# Generic_Module.net
KiCad netlist of a schematic drawn in Altium Designer
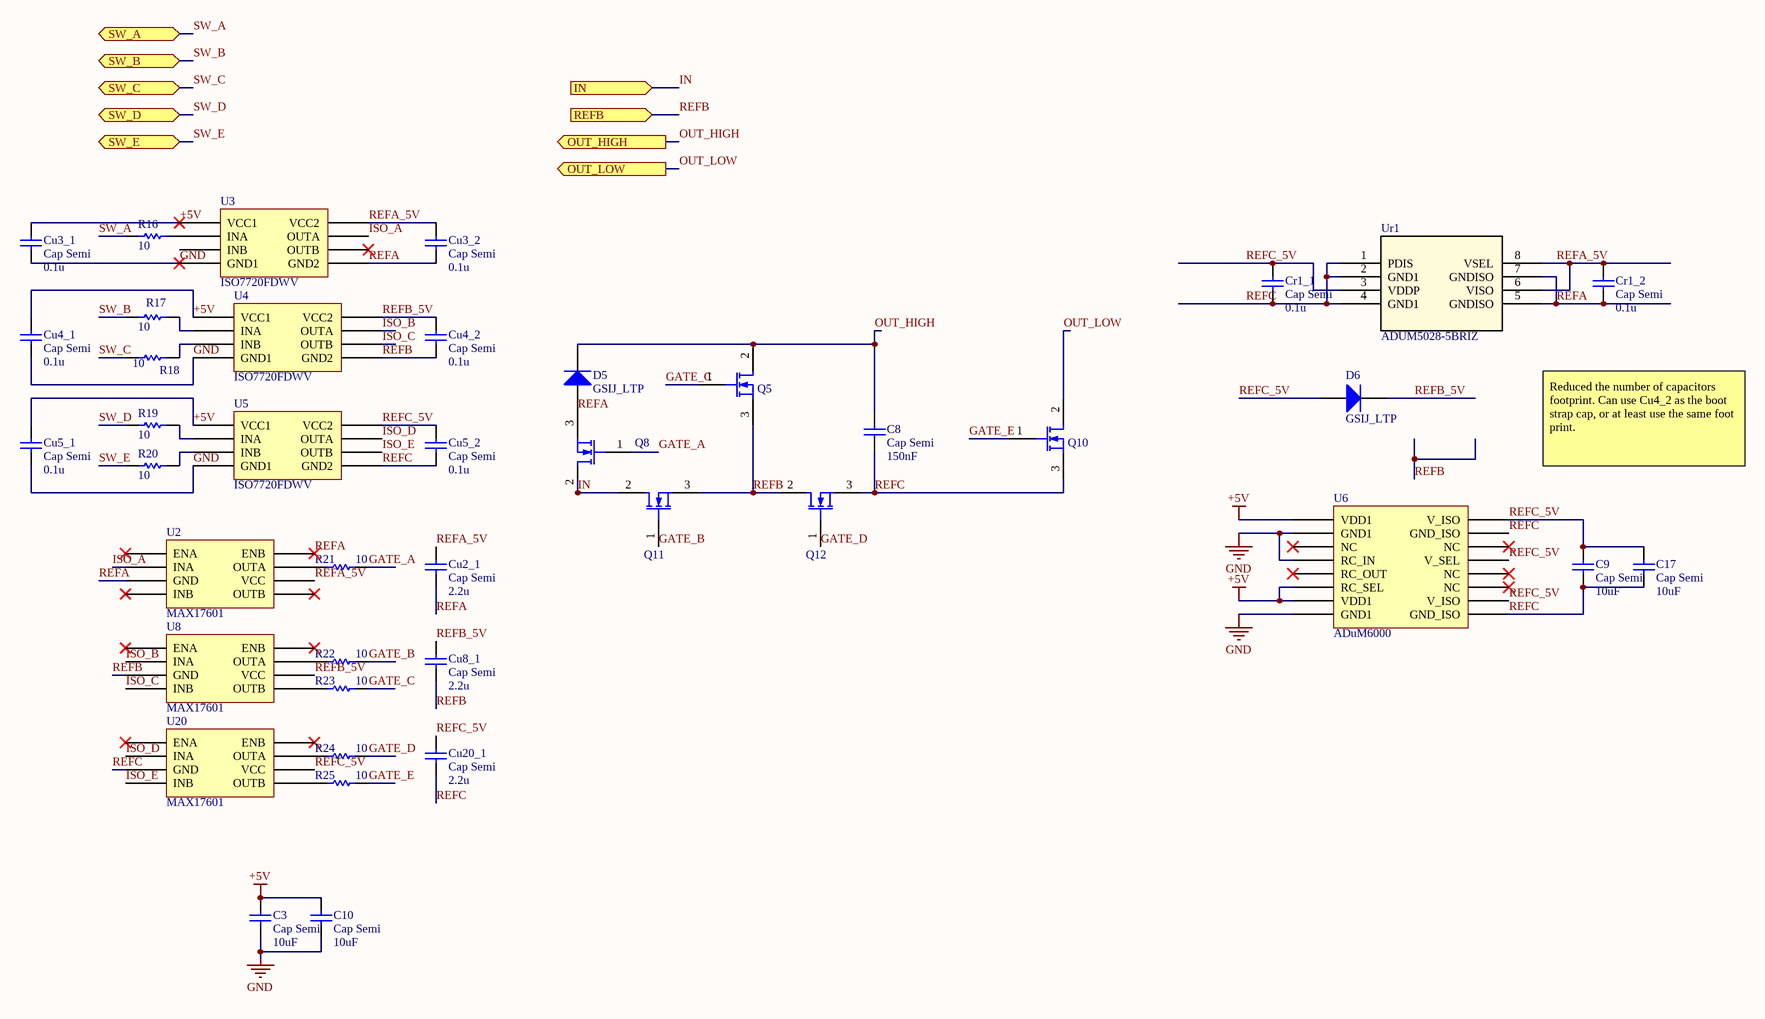
[diagram p0: Generic_Module.SchDoc]

(export (version "E")
  (design (tool "Eeschema 10.0.6"))
  (components
    (comp (ref "C3")
      (value "Cap Semi")
      (footprint "1608[0603]")
      (description "Capacitor (Semiconductor SIM Model)")
      (fields (field (name "ALTIUM_VALUE") "10uF") (field (name "PUBLISHER") "Altium Limited"))
      (libsource (lib "Miscellaneous Devices") (part "Cap Semi"))
    )
    (comp (ref "C8")
      (value "Cap Semi")
      (footprint "1812")
      (description "Capacitor (Semiconductor SIM Model)")
      (fields (field (name "ALTIUM_VALUE") "150nF") (field (name "PUBLISHER") "Altium Limited"))
      (libsource (lib "Miscellaneous Devices") (part "Cap Semi"))
    )
    (comp (ref "C9")
      (value "Cap Semi")
      (footprint "J1-0603")
      (description "Capacitor (Semiconductor SIM Model)")
      (fields (field (name "ALTIUM_VALUE") "10uF") (field (name "PUBLISHER") "Altium Limited"))
      (libsource (lib "Miscellaneous Devices") (part "Cap Semi"))
    )
    (comp (ref "C10")
      (value "Cap Semi")
      (footprint "1608[0603]")
      (description "Capacitor (Semiconductor SIM Model)")
      (fields (field (name "ALTIUM_VALUE") "10uF") (field (name "PUBLISHER") "Altium Limited"))
      (libsource (lib "Miscellaneous Devices") (part "Cap Semi"))
    )
    (comp (ref "C17")
      (value "Cap Semi")
      (footprint "J1-0603")
      (description "Capacitor (Semiconductor SIM Model)")
      (fields (field (name "ALTIUM_VALUE") "10uF") (field (name "PUBLISHER") "Altium Limited"))
      (libsource (lib "Miscellaneous Devices") (part "Cap Semi"))
    )
    (comp (ref "Cr1_1")
      (value "Cap Semi")
      (footprint "J1-0603")
      (description "Capacitor (Semiconductor SIM Model)")
      (fields (field (name "ALTIUM_VALUE") "0.1u") (field (name "PUBLISHER") "Altium Limited"))
      (libsource (lib "Miscellaneous Devices") (part "Cap Semi"))
    )
    (comp (ref "Cr1_2")
      (value "Cap Semi")
      (footprint "J1-0603")
      (description "Capacitor (Semiconductor SIM Model)")
      (fields (field (name "ALTIUM_VALUE") "0.1u") (field (name "PUBLISHER") "Altium Limited"))
      (libsource (lib "Miscellaneous Devices") (part "Cap Semi"))
    )
    (comp (ref "Cu2_1")
      (value "Cap Semi")
      (footprint "1608[0603]")
      (description "Capacitor (Semiconductor SIM Model)")
      (fields (field (name "ALTIUM_VALUE") "2.2u") (field (name "PUBLISHER") "Altium Limited"))
      (libsource (lib "SCMLI_V3_1") (part "Cap Semi"))
    )
    (comp (ref "Cu3_1")
      (value "Cap Semi")
      (footprint "C1206")
      (description "Capacitor (Semiconductor SIM Model)")
      (fields (field (name "ALTIUM_VALUE") "0.1u") (field (name "PUBLISHER") "Altium Limited"))
      (libsource (lib "SCMLI_V3_1") (part "Cap Semi"))
    )
    (comp (ref "Cu3_2")
      (value "Cap Semi")
      (footprint "C1206")
      (description "Capacitor (Semiconductor SIM Model)")
      (fields (field (name "ALTIUM_VALUE") "0.1u") (field (name "PUBLISHER") "Altium Limited"))
      (libsource (lib "SCMLI_V3_1") (part "Cap Semi"))
    )
    (comp (ref "Cu4_1")
      (value "Cap Semi")
      (footprint "C1206")
      (description "Capacitor (Semiconductor SIM Model)")
      (fields (field (name "ALTIUM_VALUE") "0.1u") (field (name "PUBLISHER") "Altium Limited"))
      (libsource (lib "SCMLI_V3_1") (part "Cap Semi"))
    )
    (comp (ref "Cu4_2")
      (value "Cap Semi")
      (footprint "C1206")
      (description "Capacitor (Semiconductor SIM Model)")
      (fields (field (name "ALTIUM_VALUE") "0.1u") (field (name "PUBLISHER") "Altium Limited"))
      (libsource (lib "SCMLI_V3_1") (part "Cap Semi"))
    )
    (comp (ref "Cu5_1")
      (value "Cap Semi")
      (footprint "C1206")
      (description "Capacitor (Semiconductor SIM Model)")
      (fields (field (name "ALTIUM_VALUE") "0.1u") (field (name "PUBLISHER") "Altium Limited"))
      (libsource (lib "SCMLI_V3_1") (part "Cap Semi"))
    )
    (comp (ref "Cu5_2")
      (value "Cap Semi")
      (footprint "C1206")
      (description "Capacitor (Semiconductor SIM Model)")
      (fields (field (name "ALTIUM_VALUE") "0.1u") (field (name "PUBLISHER") "Altium Limited"))
      (libsource (lib "SCMLI_V3_1") (part "Cap Semi"))
    )
    (comp (ref "Cu8_1")
      (value "Cap Semi")
      (footprint "1608[0603]")
      (description "Capacitor (Semiconductor SIM Model)")
      (fields (field (name "ALTIUM_VALUE") "2.2u") (field (name "PUBLISHER") "Altium Limited"))
      (libsource (lib "SCMLI_V3_1") (part "Cap Semi"))
    )
    (comp (ref "Cu20_1")
      (value "Cap Semi")
      (footprint "1608[0603]")
      (description "Capacitor (Semiconductor SIM Model)")
      (fields (field (name "ALTIUM_VALUE") "2.2u") (field (name "PUBLISHER") "Altium Limited"))
      (libsource (lib "SCMLI_V3_1") (part "Cap Semi"))
    )
    (comp (ref "D5")
      (value "GSIJ_LTP")
      (footprint "SE30PAJ-M3")
      (libsource (lib "SCMLI_V3") (part "SE30PAJ-M3"))
    )
    (comp (ref "D6")
      (value "GSIJ_LTP")
      (footprint "SE30PAJ-M3")
      (libsource (lib "SCMLI_V3") (part "SE30PAJ-M3"))
    )
    (comp (ref "Q5")
      (value "IPN80R1K2P7")
      (footprint "SOT233-3")
      (libsource (lib "SCMLI_V3") (part "IPN80R1K2P7"))
    )
    (comp (ref "Q8")
      (value "IPN80R1K2P7")
      (footprint "SOT233-3")
      (libsource (lib "SCMLI_V3") (part "IPN80R1K2P7"))
    )
    (comp (ref "Q10")
      (value "IPN80R1K2P7")
      (footprint "SOT233-3")
      (libsource (lib "SCMLI_V3") (part "IPN80R1K2P7"))
    )
    (comp (ref "Q11")
      (value "IPN80R1K2P7")
      (footprint "SOT233-3")
      (libsource (lib "SCMLI_V3") (part "IPN80R1K2P7"))
    )
    (comp (ref "Q12")
      (value "IPN80R1K2P7")
      (footprint "SOT233-3")
      (libsource (lib "SCMLI_V3") (part "IPN80R1K2P7"))
    )
    (comp (ref "R16")
      (value "10")
      (footprint "1608[0603]")
      (description "Resistor 0402 / 0603 / 0805")
      (libsource (lib "Miscellaneous Devices") (part "Res1"))
    )
    (comp (ref "R17")
      (value "10")
      (footprint "1608[0603]")
      (description "Resistor 0402 / 0603 / 0805")
      (libsource (lib "Miscellaneous Devices") (part "Res1"))
    )
    (comp (ref "R18")
      (value "10")
      (footprint "1608[0603]")
      (description "Resistor 0402 / 0603 / 0805")
      (libsource (lib "Miscellaneous Devices") (part "Res1"))
    )
    (comp (ref "R19")
      (value "10")
      (footprint "1608[0603]")
      (description "Resistor 0402 / 0603 / 0805")
      (libsource (lib "Miscellaneous Devices") (part "Res1"))
    )
    (comp (ref "R20")
      (value "10")
      (footprint "1608[0603]")
      (description "Resistor 0402 / 0603 / 0805")
      (libsource (lib "Miscellaneous Devices") (part "Res1"))
    )
    (comp (ref "R21")
      (value "10")
      (footprint "1608[0603]")
      (description "Resistor 0402 / 0603 / 0805")
      (libsource (lib "Miscellaneous Devices") (part "Res1"))
    )
    (comp (ref "R22")
      (value "10")
      (footprint "1608[0603]")
      (description "Resistor 0402 / 0603 / 0805")
      (libsource (lib "Miscellaneous Devices") (part "Res1"))
    )
    (comp (ref "R23")
      (value "10")
      (footprint "1608[0603]")
      (description "Resistor 0402 / 0603 / 0805")
      (libsource (lib "Miscellaneous Devices") (part "Res1"))
    )
    (comp (ref "R24")
      (value "10")
      (footprint "1608[0603]")
      (description "Resistor 0402 / 0603 / 0805")
      (libsource (lib "Miscellaneous Devices") (part "Res1"))
    )
    (comp (ref "R25")
      (value "10")
      (footprint "1608[0603]")
      (description "Resistor 0402 / 0603 / 0805")
      (libsource (lib "Miscellaneous Devices") (part "Res1"))
    )
    (comp (ref "U2")
      (value "MAX17601")
      (footprint "DFN-8_DD")
      (libsource (lib "SCMLI_V3_1") (part "MAX17601"))
    )
    (comp (ref "U3")
      (value "ISO7720FDWV")
      (footprint "TI_DWV")
      (libsource (lib "SCMLI_V3_1") (part "ISO7720FDWV"))
    )
    (comp (ref "U4")
      (value "ISO7720FDWV")
      (footprint "TI_DWV")
      (libsource (lib "SCMLI_V3_1") (part "ISO7720FDWV"))
    )
    (comp (ref "U5")
      (value "ISO7720FDWV")
      (footprint "TI_DWV")
      (libsource (lib "SCMLI_V3_1") (part "ISO7720FDWV"))
    )
    (comp (ref "U6")
      (value "ADuM6000")
      (footprint "SOIC127P1030X265-16N")
      (description "Isolatd 5V-5V DCDC power supply")
      (libsource (lib "SCMLI_V3") (part "ADuM6000"))
    )
    (comp (ref "U8")
      (value "MAX17601")
      (footprint "DFN-8_DD")
      (libsource (lib "SCMLI_V3_1") (part "MAX17601"))
    )
    (comp (ref "U20")
      (value "MAX17601")
      (footprint "DFN-8_DD")
      (libsource (lib "SCMLI_V3_1") (part "MAX17601"))
    )
    (comp (ref "Ur1")
      (value "ADUM5028-5BRIZ")
      (footprint "RI_8_1")
      (description "No Description Available")
      (fields (field (name "COPYRIGHT") "Copyright (C) 2018 Accelerated Designs. All rights reserved"))
      (libsource (lib "SCMLI_V3_1") (part "ADUM5028-5BRIZ"))
    )
  )
  (nets
    (net (code "1") (name "+5V") (class "Default")
      (node (ref "C10") (pin "2") (pinfunction "2_2") (pintype "passive"))
      (node (ref "C3") (pin "2") (pinfunction "2_2") (pintype "passive"))
      (node (ref "Cu3_1") (pin "2") (pinfunction "2_2") (pintype "passive"))
      (node (ref "Cu4_1") (pin "2") (pinfunction "2_2") (pintype "passive"))
      (node (ref "Cu5_1") (pin "2") (pinfunction "2_2") (pintype "passive"))
      (node (ref "U3") (pin "1") (pinfunction "VCC1_1") (pintype "passive"))
      (node (ref "U4") (pin "1") (pinfunction "VCC1_1") (pintype "passive"))
      (node (ref "U5") (pin "1") (pinfunction "VCC1_1") (pintype "passive"))
      (node (ref "U6") (pin "1") (pinfunction "VDD1_1") (pintype "passive"))
      (node (ref "U6") (pin "6") (pinfunction "RC_SEL_6") (pintype "passive"))
      (node (ref "U6") (pin "7") (pinfunction "VDD1_7") (pintype "passive"))
    )
    (net (code "2") (name "/GATE_A") (class "Default")
      (node (ref "Q8") (pin "1") (pinfunction "1_1") (pintype "passive"))
      (node (ref "R21") (pin "2") (pinfunction "2_2") (pintype "passive"))
    )
    (net (code "3") (name "/GATE_B") (class "Default")
      (node (ref "Q11") (pin "1") (pinfunction "1_1") (pintype "passive"))
      (node (ref "R22") (pin "2") (pinfunction "2_2") (pintype "passive"))
    )
    (net (code "4") (name "/GATE_C") (class "Default")
      (node (ref "Q5") (pin "1") (pinfunction "1_1") (pintype "passive"))
      (node (ref "R23") (pin "2") (pinfunction "2_2") (pintype "passive"))
    )
    (net (code "5") (name "/GATE_D") (class "Default")
      (node (ref "Q12") (pin "1") (pinfunction "1_1") (pintype "passive"))
      (node (ref "R24") (pin "2") (pinfunction "2_2") (pintype "passive"))
    )
    (net (code "6") (name "/GATE_E") (class "Default")
      (node (ref "Q10") (pin "1") (pinfunction "1_1") (pintype "passive"))
      (node (ref "R25") (pin "2") (pinfunction "2_2") (pintype "passive"))
    )
    (net (code "7") (name "/IN") (class "Default")
      (node (ref "Q11") (pin "2") (pinfunction "2_2") (pintype "passive"))
      (node (ref "Q8") (pin "2") (pinfunction "2_2") (pintype "passive"))
    )
    (net (code "8") (name "/ISO_A") (class "Default")
      (node (ref "U2") (pin "2") (pinfunction "INA_2") (pintype "passive"))
      (node (ref "U3") (pin "7") (pinfunction "OUTA_7") (pintype "passive"))
    )
    (net (code "9") (name "/ISO_B") (class "Default")
      (node (ref "U4") (pin "7") (pinfunction "OUTA_7") (pintype "passive"))
      (node (ref "U8") (pin "2") (pinfunction "INA_2") (pintype "passive"))
    )
    (net (code "10") (name "/ISO_C") (class "Default")
      (node (ref "U4") (pin "6") (pinfunction "OUTB_6") (pintype "passive"))
      (node (ref "U8") (pin "4") (pinfunction "INB_4") (pintype "passive"))
    )
    (net (code "11") (name "/ISO_D") (class "Default")
      (node (ref "U20") (pin "2") (pinfunction "INA_2") (pintype "passive"))
      (node (ref "U5") (pin "7") (pinfunction "OUTA_7") (pintype "passive"))
    )
    (net (code "12") (name "/ISO_E") (class "Default")
      (node (ref "U20") (pin "4") (pinfunction "INB_4") (pintype "passive"))
      (node (ref "U5") (pin "6") (pinfunction "OUTB_6") (pintype "passive"))
    )
    (net (code "13") (name "/OUT_HIGH") (class "Default")
      (node (ref "C8") (pin "2") (pinfunction "2_2") (pintype "passive"))
      (node (ref "D5") (pin "2") (pinfunction "K_2") (pintype "passive"))
      (node (ref "Q5") (pin "2") (pinfunction "2_2") (pintype "passive"))
    )
    (net (code "14") (name "/OUT_LOW") (class "Default")
      (node (ref "Q10") (pin "2") (pinfunction "2_2") (pintype "passive"))
    )
    (net (code "15") (name "/REFA") (class "Default")
      (node (ref "Cr1_2") (pin "1") (pinfunction "1_1") (pintype "passive"))
      (node (ref "Cu2_1") (pin "1") (pinfunction "1_1") (pintype "passive"))
      (node (ref "Cu3_2") (pin "1") (pinfunction "1_1") (pintype "passive"))
      (node (ref "D5") (pin "1") (pinfunction "A_1") (pintype "passive"))
      (node (ref "Q8") (pin "3") (pinfunction "3_3") (pintype "passive"))
      (node (ref "U2") (pin "3") (pinfunction "GND_3") (pintype "passive"))
      (node (ref "U2") (pin "8") (pinfunction "ENB_8") (pintype "passive"))
      (node (ref "U3") (pin "5") (pinfunction "GND2_5") (pintype "passive"))
      (node (ref "Ur1") (pin "5") (pinfunction "GNDISO_5") (pintype "passive"))
      (node (ref "Ur1") (pin "7") (pinfunction "GNDISO_7") (pintype "passive"))
    )
    (net (code "16") (name "/REFA_5V") (class "Default")
      (node (ref "Cr1_2") (pin "2") (pinfunction "2_2") (pintype "passive"))
      (node (ref "Cu2_1") (pin "2") (pinfunction "2_2") (pintype "passive"))
      (node (ref "Cu3_2") (pin "2") (pinfunction "2_2") (pintype "passive"))
      (node (ref "U2") (pin "6") (pinfunction "VCC_6") (pintype "passive"))
      (node (ref "U3") (pin "8") (pinfunction "VCC2_8") (pintype "passive"))
      (node (ref "Ur1") (pin "6") (pinfunction "VISO_6") (pintype "passive"))
      (node (ref "Ur1") (pin "8") (pinfunction "VSEL_8") (pintype "passive"))
    )
    (net (code "17") (name "/REFB") (class "Default")
      (node (ref "Cu4_2") (pin "1") (pinfunction "1_1") (pintype "passive"))
      (node (ref "Cu8_1") (pin "1") (pinfunction "1_1") (pintype "passive"))
      (node (ref "Q11") (pin "3") (pinfunction "3_3") (pintype "passive"))
      (node (ref "Q12") (pin "2") (pinfunction "2_2") (pintype "passive"))
      (node (ref "Q5") (pin "3") (pinfunction "3_3") (pintype "passive"))
      (node (ref "U4") (pin "5") (pinfunction "GND2_5") (pintype "passive"))
      (node (ref "U8") (pin "3") (pinfunction "GND_3") (pintype "passive"))
    )
    (net (code "18") (name "/REFB_5V") (class "Default")
      (node (ref "Cu4_2") (pin "2") (pinfunction "2_2") (pintype "passive"))
      (node (ref "Cu8_1") (pin "2") (pinfunction "2_2") (pintype "passive"))
      (node (ref "D6") (pin "2") (pinfunction "K_2") (pintype "passive"))
      (node (ref "U4") (pin "8") (pinfunction "VCC2_8") (pintype "passive"))
      (node (ref "U8") (pin "6") (pinfunction "VCC_6") (pintype "passive"))
    )
    (net (code "19") (name "/REFC") (class "Default")
      (node (ref "C17") (pin "1") (pinfunction "1_1") (pintype "passive"))
      (node (ref "C8") (pin "1") (pinfunction "1_1") (pintype "passive"))
      (node (ref "C9") (pin "1") (pinfunction "1_1") (pintype "passive"))
      (node (ref "Cr1_1") (pin "1") (pinfunction "1_1") (pintype "passive"))
      (node (ref "Cu20_1") (pin "1") (pinfunction "1_1") (pintype "passive"))
      (node (ref "Cu5_2") (pin "1") (pinfunction "1_1") (pintype "passive"))
      (node (ref "Q10") (pin "3") (pinfunction "3_3") (pintype "passive"))
      (node (ref "Q12") (pin "3") (pinfunction "3_3") (pintype "passive"))
      (node (ref "U20") (pin "3") (pinfunction "GND_3") (pintype "passive"))
      (node (ref "U5") (pin "5") (pinfunction "GND2_5") (pintype "passive"))
      (node (ref "U6") (pin "15") (pinfunction "GND_ISO_15") (pintype "passive"))
      (node (ref "U6") (pin "9") (pinfunction "GND_ISO_9") (pintype "passive"))
      (node (ref "Ur1") (pin "1") (pinfunction "PDIS_1") (pintype "passive"))
      (node (ref "Ur1") (pin "2") (pinfunction "GND1_2") (pintype "passive"))
      (node (ref "Ur1") (pin "4") (pinfunction "GND1_4") (pintype "passive"))
    )
    (net (code "20") (name "/REFC_5V") (class "Default")
      (node (ref "C17") (pin "2") (pinfunction "2_2") (pintype "passive"))
      (node (ref "C9") (pin "2") (pinfunction "2_2") (pintype "passive"))
      (node (ref "Cr1_1") (pin "2") (pinfunction "2_2") (pintype "passive"))
      (node (ref "Cu20_1") (pin "2") (pinfunction "2_2") (pintype "passive"))
      (node (ref "Cu5_2") (pin "2") (pinfunction "2_2") (pintype "passive"))
      (node (ref "D6") (pin "1") (pinfunction "A_1") (pintype "passive"))
      (node (ref "U20") (pin "6") (pinfunction "VCC_6") (pintype "passive"))
      (node (ref "U5") (pin "8") (pinfunction "VCC2_8") (pintype "passive"))
      (node (ref "U6") (pin "10") (pinfunction "V_ISO_10") (pintype "passive"))
      (node (ref "U6") (pin "13") (pinfunction "V_SEL_13") (pintype "passive"))
      (node (ref "U6") (pin "16") (pinfunction "V_ISO_16") (pintype "passive"))
      (node (ref "Ur1") (pin "3") (pinfunction "VDDP_3") (pintype "passive"))
    )
    (net (code "21") (name "/SW_A") (class "Default")
      (node (ref "R16") (pin "2") (pinfunction "2_2") (pintype "passive"))
    )
    (net (code "22") (name "/SW_B") (class "Default")
      (node (ref "R17") (pin "2") (pinfunction "2_2") (pintype "passive"))
    )
    (net (code "23") (name "/SW_C") (class "Default")
      (node (ref "R18") (pin "1") (pinfunction "1_1") (pintype "passive"))
    )
    (net (code "24") (name "/SW_D") (class "Default")
      (node (ref "R19") (pin "2") (pinfunction "2_2") (pintype "passive"))
    )
    (net (code "25") (name "/SW_E") (class "Default")
      (node (ref "R20") (pin "2") (pinfunction "2_2") (pintype "passive"))
    )
    (net (code "26") (name "GND") (class "Default")
      (node (ref "C10") (pin "1") (pinfunction "1_1") (pintype "passive"))
      (node (ref "C3") (pin "1") (pinfunction "1_1") (pintype "passive"))
      (node (ref "Cu3_1") (pin "1") (pinfunction "1_1") (pintype "passive"))
      (node (ref "Cu4_1") (pin "1") (pinfunction "1_1") (pintype "passive"))
      (node (ref "Cu5_1") (pin "1") (pinfunction "1_1") (pintype "passive"))
      (node (ref "U3") (pin "4") (pinfunction "GND1_4") (pintype "passive"))
      (node (ref "U4") (pin "4") (pinfunction "GND1_4") (pintype "passive"))
      (node (ref "U5") (pin "4") (pinfunction "GND1_4") (pintype "passive"))
      (node (ref "U6") (pin "2") (pinfunction "GND1_2") (pintype "passive"))
      (node (ref "U6") (pin "4") (pinfunction "RC_IN_4") (pintype "passive"))
      (node (ref "U6") (pin "8") (pinfunction "GND1_8") (pintype "passive"))
    )
    (net (code "27") (name "Net-(U2-OUTA)") (class "Default")
      (node (ref "R21") (pin "1") (pinfunction "1_1") (pintype "passive"))
      (node (ref "U2") (pin "7") (pinfunction "OUTA_7") (pintype "passive"))
    )
    (net (code "28") (name "Net-(U3-INA)") (class "Default")
      (node (ref "R16") (pin "1") (pinfunction "1_1") (pintype "passive"))
      (node (ref "U3") (pin "2") (pinfunction "INA_2") (pintype "passive"))
    )
    (net (code "29") (name "Net-(U4-INA)") (class "Default")
      (node (ref "R17") (pin "1") (pinfunction "1_1") (pintype "passive"))
      (node (ref "U4") (pin "2") (pinfunction "INA_2") (pintype "passive"))
    )
    (net (code "30") (name "Net-(U4-INB)") (class "Default")
      (node (ref "R18") (pin "2") (pinfunction "2_2") (pintype "passive"))
      (node (ref "U4") (pin "3") (pinfunction "INB_3") (pintype "passive"))
    )
    (net (code "31") (name "Net-(U5-INA)") (class "Default")
      (node (ref "R19") (pin "1") (pinfunction "1_1") (pintype "passive"))
      (node (ref "U5") (pin "2") (pinfunction "INA_2") (pintype "passive"))
    )
    (net (code "32") (name "Net-(U5-INB)") (class "Default")
      (node (ref "R20") (pin "1") (pinfunction "1_1") (pintype "passive"))
      (node (ref "U5") (pin "3") (pinfunction "INB_3") (pintype "passive"))
    )
    (net (code "33") (name "Net-(U8-OUTA)") (class "Default")
      (node (ref "R22") (pin "1") (pinfunction "1_1") (pintype "passive"))
      (node (ref "U8") (pin "7") (pinfunction "OUTA_7") (pintype "passive"))
    )
    (net (code "34") (name "Net-(U8-OUTB)") (class "Default")
      (node (ref "R23") (pin "1") (pinfunction "1_1") (pintype "passive"))
      (node (ref "U8") (pin "5") (pinfunction "OUTB_5") (pintype "passive"))
    )
    (net (code "35") (name "Net-(U20-OUTA)") (class "Default")
      (node (ref "R24") (pin "1") (pinfunction "1_1") (pintype "passive"))
      (node (ref "U20") (pin "7") (pinfunction "OUTA_7") (pintype "passive"))
    )
    (net (code "36") (name "Net-(U20-OUTB)") (class "Default")
      (node (ref "R25") (pin "1") (pinfunction "1_1") (pintype "passive"))
      (node (ref "U20") (pin "5") (pinfunction "OUTB_5") (pintype "passive"))
    )
    (net (code "37") (name "unconnected-(U2-ENA-Pad1)") (class "Default")
      (node (ref "U2") (pin "1") (pinfunction "ENA_1") (pintype "passive+no_connect"))
    )
    (net (code "38") (name "unconnected-(U2-INB-Pad4)") (class "Default")
      (node (ref "U2") (pin "4") (pinfunction "INB_4") (pintype "passive+no_connect"))
    )
    (net (code "39") (name "unconnected-(U2-OUTB-Pad5)") (class "Default")
      (node (ref "U2") (pin "5") (pinfunction "OUTB_5") (pintype "passive+no_connect"))
    )
    (net (code "40") (name "unconnected-(U3-INB-Pad3)") (class "Default")
      (node (ref "U3") (pin "3") (pinfunction "INB_3") (pintype "passive"))
    )
    (net (code "41") (name "unconnected-(U3-OUTB-Pad6)") (class "Default")
      (node (ref "U3") (pin "6") (pinfunction "OUTB_6") (pintype "passive+no_connect"))
    )
    (net (code "42") (name "unconnected-(U6-NC-Pad3)") (class "Default")
      (node (ref "U6") (pin "3") (pinfunction "NC_3") (pintype "passive+no_connect"))
    )
    (net (code "43") (name "unconnected-(U6-NC-Pad11)") (class "Default")
      (node (ref "U6") (pin "11") (pinfunction "NC_11") (pintype "passive+no_connect"))
    )
    (net (code "44") (name "unconnected-(U6-NC-Pad12)") (class "Default")
      (node (ref "U6") (pin "12") (pinfunction "NC_12") (pintype "passive+no_connect"))
    )
    (net (code "45") (name "unconnected-(U6-NC-Pad14)") (class "Default")
      (node (ref "U6") (pin "14") (pinfunction "NC_14") (pintype "passive+no_connect"))
    )
    (net (code "46") (name "unconnected-(U6-RC_OUT-Pad5)") (class "Default")
      (node (ref "U6") (pin "5") (pinfunction "RC_OUT_5") (pintype "passive+no_connect"))
    )
    (net (code "47") (name "unconnected-(U8-ENA-Pad1)") (class "Default")
      (node (ref "U8") (pin "1") (pinfunction "ENA_1") (pintype "passive+no_connect"))
    )
    (net (code "48") (name "unconnected-(U8-ENB-Pad8)") (class "Default")
      (node (ref "U8") (pin "8") (pinfunction "ENB_8") (pintype "passive+no_connect"))
    )
    (net (code "49") (name "unconnected-(U20-ENA-Pad1)") (class "Default")
      (node (ref "U20") (pin "1") (pinfunction "ENA_1") (pintype "passive+no_connect"))
    )
    (net (code "50") (name "unconnected-(U20-ENB-Pad8)") (class "Default")
      (node (ref "U20") (pin "8") (pinfunction "ENB_8") (pintype "passive+no_connect"))
    )
  )
)
